# Sport_Analyzer_Chronojump.net
KiCad netlist of a schematic drawn in EAGLE
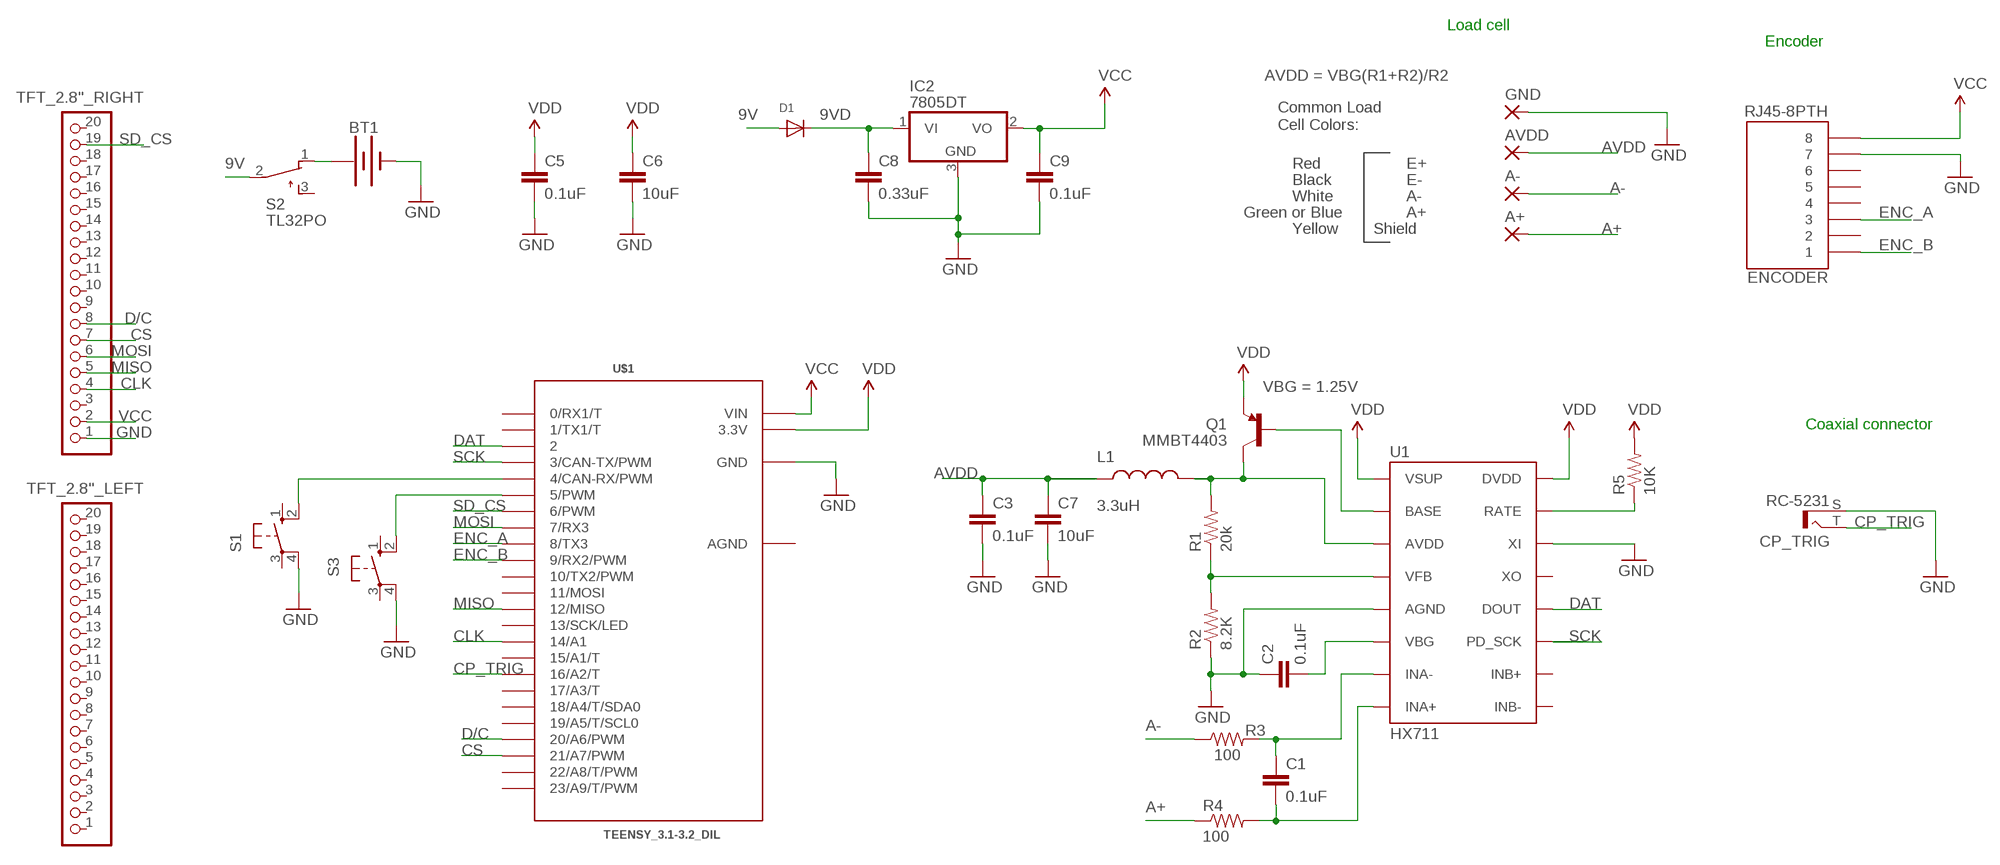
[diagram p0: schematic, sheet 1]

(export (version "E")
  (design (tool "Eeschema 10.0.6"))
  (components
    (comp (ref "A+")
      (value "3,81/1,4")
      (footprint "eagle-import:3,81_1,4")
      (libsource (lib "eagle-import") (part "3,81/1,4"))
    )
    (comp (ref "A-")
      (value "3,81/1,4")
      (footprint "eagle-import:3,81_1,4")
      (libsource (lib "eagle-import") (part "3,81/1,4"))
    )
    (comp (ref "AVDD")
      (value "3,81/1,4")
      (footprint "eagle-import:3,81_1,4")
      (libsource (lib "eagle-import") (part "3,81/1,4"))
    )
    (comp (ref "BT1")
      (value "BATTERY-9V")
      (footprint "eagle-import:BATTCON_9V")
      (libsource (lib "eagle-import") (part "BATTERY-9V"))
    )
    (comp (ref "C1")
      (value "0.1uF")
      (footprint "eagle-import:0603-CAP")
      (libsource (lib "eagle-import") (part "0.1UF-25V-5%(0603)"))
    )
    (comp (ref "C2")
      (value "0.1uF")
      (footprint "eagle-import:0603-CAP")
      (libsource (lib "eagle-import") (part "0.1UF-25V-5%(0603)"))
    )
    (comp (ref "C3")
      (value "0.1uF")
      (footprint "eagle-import:0603-CAP")
      (libsource (lib "eagle-import") (part "0.1UF-25V-5%(0603)"))
    )
    (comp (ref "C5")
      (value "0.1uF")
      (footprint "eagle-import:0603-CAP")
      (libsource (lib "eagle-import") (part "0.1UF-25V-5%(0603)"))
    )
    (comp (ref "C6")
      (value "10uF")
      (footprint "eagle-import:1210")
      (libsource (lib "eagle-import") (part "10UF50V20%(1210)"))
    )
    (comp (ref "C7")
      (value "10uF")
      (footprint "eagle-import:1210")
      (libsource (lib "eagle-import") (part "10UF50V20%(1210)"))
    )
    (comp (ref "C8")
      (value "0.33uF")
      (footprint "eagle-import:0603-CAP")
      (libsource (lib "eagle-import") (part "0.1UF-25V-5%(0603)"))
    )
    (comp (ref "C9")
      (value "0.1uF")
      (footprint "eagle-import:0603-CAP")
      (libsource (lib "eagle-import") (part "0.1UF-25V-5%(0603)"))
    )
    (comp (ref "CP_TRIG")
      (value "RC-5231")
      (footprint "eagle-import:RC-5231")
      (libsource (lib "eagle-import") (part "RC-5231"))
    )
    (comp (ref "D1")
      (value "DIODESOD-123")
      (footprint "eagle-import:SOD-123")
      (libsource (lib "eagle-import") (part "DIODESOD-123"))
    )
    (comp (ref "ENCODER")
      (value "RJ45-8PTH")
      (footprint "eagle-import:RJ45-8")
      (libsource (lib "eagle-import") (part "RJ45-8PTH"))
    )
    (comp (ref "GND")
      (value "3,81/1,4")
      (footprint "eagle-import:3,81_1,4")
      (libsource (lib "eagle-import") (part "3,81/1,4"))
    )
    (comp (ref "IC2")
      (value "7805DT")
      (footprint "eagle-import:TO252")
      (libsource (lib "eagle-import") (part "78DT05"))
    )
    (comp (ref "L1")
      (value "3.3uH")
      (footprint "eagle-import:0805")
      (libsource (lib "eagle-import") (part "INDUCTOR0805-IND"))
    )
    (comp (ref "Q1")
      (value "MMBT4403")
      (footprint "eagle-import:SOT23-3")
      (libsource (lib "eagle-import") (part "TRANSISTOR_PNPMMBT4403"))
    )
    (comp (ref "R1")
      (value "20k")
      (footprint "eagle-import:0603-RES")
      (libsource (lib "eagle-import") (part "20KOHM1/10W1%(0603)"))
    )
    (comp (ref "R2")
      (value "8.2K")
      (footprint "eagle-import:0603-RES")
      (libsource (lib "eagle-import") (part "8.2KOHM-1/10W-5%(0603)"))
    )
    (comp (ref "R3")
      (value "100")
      (footprint "eagle-import:0603-RES")
      (libsource (lib "eagle-import") (part "100OHM-1/10W-1%(0603)"))
    )
    (comp (ref "R4")
      (value "100")
      (footprint "eagle-import:0603-RES")
      (libsource (lib "eagle-import") (part "100OHM-1/10W-1%(0603)"))
    )
    (comp (ref "R5")
      (value "10K")
      (footprint "eagle-import:0603-RES")
      (libsource (lib "eagle-import") (part "10KOHM-1/10W-1%(0603)0603"))
    )
    (comp (ref "S1")
      (value "10-XX")
      (footprint "eagle-import:B3F-10XX")
      (fields (field (name "MPN") "B3F-1000"))
      (libsource (lib "eagle-import") (part "10-XX"))
    )
    (comp (ref "S2")
      (value "TL32PO")
      (footprint "eagle-import:TL3XPO")
      (libsource (lib "eagle-import") (part "TL32PO"))
    )
    (comp (ref "S3")
      (value "10-XX")
      (footprint "eagle-import:B3F-10XX")
      (fields (field (name "MPN") "B3F-1000"))
      (libsource (lib "eagle-import") (part "10-XX"))
    )
    (comp (ref "TFT_2.8\"_LEFT")
      (value "PINHD-1X20")
      (footprint "eagle-import:1X20")
      (libsource (lib "eagle-import") (part "PINHD-1X20"))
    )
    (comp (ref "TFT_2.8\"_RIGHT")
      (value "PINHD-1X20")
      (footprint "eagle-import:1X20")
      (libsource (lib "eagle-import") (part "PINHD-1X20"))
    )
    (comp (ref "U$1")
      (value "TEENSY_3.1-3.2_DIL")
      (footprint "eagle-import:TEENSY_3.0-3.2&LC_DIL")
      (libsource (lib "eagle-import") (part "TEENSY_3.1-3.2_DIL"))
    )
    (comp (ref "U1")
      (value "HX711")
      (footprint "eagle-import:SO16")
      (libsource (lib "eagle-import") (part "HX711HX711"))
    )
  )
  (nets
    (net (code "1") (name "/9V") (class "Default")
      (node (ref "D1") (pin "A") (pinfunction "A_A") (pintype "passive"))
      (node (ref "S2") (pin "2") (pinfunction "P_2") (pintype "passive"))
    )
    (net (code "2") (name "/9VD") (class "Default")
      (node (ref "C8") (pin "1") (pinfunction "1_1") (pintype "passive"))
      (node (ref "D1") (pin "C") (pinfunction "C_C") (pintype "passive"))
      (node (ref "IC2") (pin "1") (pinfunction "VI_1") (pintype "input"))
    )
    (net (code "3") (name "/A+") (class "Default")
      (node (ref "A+") (pin "1") (pinfunction "P_1") (pintype "passive"))
      (node (ref "R4") (pin "1") (pinfunction "1_1") (pintype "passive"))
    )
    (net (code "4") (name "/A-") (class "Default")
      (node (ref "A-") (pin "1") (pinfunction "P_1") (pintype "passive"))
      (node (ref "R3") (pin "1") (pinfunction "1_1") (pintype "passive"))
    )
    (net (code "5") (name "/AGND") (class "Default")
      (node (ref "U$1") (pin "AGND") (pinfunction "AGND_AGND") (pintype "power_in"))
    )
    (net (code "6") (name "/AVDD") (class "Default")
      (node (ref "AVDD") (pin "1") (pinfunction "P_1") (pintype "passive"))
      (node (ref "C3") (pin "1") (pinfunction "1_1") (pintype "passive"))
      (node (ref "C7") (pin "1") (pinfunction "1_1") (pintype "passive"))
      (node (ref "L1") (pin "1") (pinfunction "1_1") (pintype "passive"))
    )
    (net (code "7") (name "/CLK") (class "Default")
      (node (ref "TFT_2.8\"_RIGHT") (pin "4") (pinfunction "4_4") (pintype "passive"))
      (node (ref "U$1") (pin "14/A0") (pinfunction "14/A1_14/A0") (pintype "bidirectional"))
    )
    (net (code "8") (name "/CP_TRIG") (class "Default")
      (node (ref "CP_TRIG") (pin "T") (pinfunction "T_T") (pintype "passive"))
      (node (ref "U$1") (pin "16/A2") (pinfunction "16/A2/T_16/A2") (pintype "bidirectional"))
    )
    (net (code "9") (name "/CS") (class "Default")
      (node (ref "TFT_2.8\"_RIGHT") (pin "7") (pinfunction "7_7") (pintype "passive"))
      (node (ref "U$1") (pin "21/A7") (pinfunction "21/A7/PWM_21/A7") (pintype "bidirectional"))
    )
    (net (code "10") (name "/DAT") (class "Default")
      (node (ref "U$1") (pin "2") (pinfunction "2_2") (pintype "bidirectional"))
      (node (ref "U1") (pin "12") (pinfunction "DOUT_12") (pintype "bidirectional"))
    )
    (net (code "11") (name "/D{slash}C") (class "Default")
      (node (ref "TFT_2.8\"_RIGHT") (pin "8") (pinfunction "8_8") (pintype "passive"))
      (node (ref "U$1") (pin "20/A6") (pinfunction "20/A6/PWM_20/A6") (pintype "bidirectional"))
    )
    (net (code "12") (name "/ENC_A") (class "Default")
      (node (ref "ENCODER") (pin "3") (pinfunction "3_3") (pintype "bidirectional"))
      (node (ref "U$1") (pin "8") (pinfunction "8/TX3_8") (pintype "bidirectional"))
    )
    (net (code "13") (name "/ENC_B") (class "Default")
      (node (ref "ENCODER") (pin "1") (pinfunction "1_1") (pintype "bidirectional"))
      (node (ref "U$1") (pin "9") (pinfunction "9/RX2/PWM_9") (pintype "bidirectional"))
    )
    (net (code "14") (name "/MISO") (class "Default")
      (node (ref "TFT_2.8\"_RIGHT") (pin "5") (pinfunction "5_5") (pintype "passive"))
      (node (ref "U$1") (pin "12") (pinfunction "12/MISO_12") (pintype "bidirectional"))
    )
    (net (code "15") (name "/MOSI") (class "Default")
      (node (ref "TFT_2.8\"_RIGHT") (pin "6") (pinfunction "6_6") (pintype "passive"))
      (node (ref "U$1") (pin "7") (pinfunction "7/RX3_7") (pintype "bidirectional"))
    )
    (net (code "16") (name "/SCK") (class "Default")
      (node (ref "U$1") (pin "3") (pinfunction "3/CAN-TX/PWM_3") (pintype "bidirectional"))
      (node (ref "U1") (pin "11") (pinfunction "PD_SCK_11") (pintype "bidirectional"))
    )
    (net (code "17") (name "/SD_CS") (class "Default")
      (node (ref "TFT_2.8\"_RIGHT") (pin "19") (pinfunction "19_19") (pintype "passive"))
      (node (ref "U$1") (pin "6") (pinfunction "6/PWM_6") (pintype "bidirectional"))
    )
    (net (code "18") (name "GND") (class "Default")
      (node (ref "BT1") (pin "-") (pinfunction "-_-") (pintype "power_in"))
      (node (ref "C2") (pin "1") (pinfunction "1_1") (pintype "passive"))
      (node (ref "C3") (pin "2") (pinfunction "2_2") (pintype "passive"))
      (node (ref "C5") (pin "2") (pinfunction "2_2") (pintype "passive"))
      (node (ref "C6") (pin "2") (pinfunction "2_2") (pintype "passive"))
      (node (ref "C7") (pin "2") (pinfunction "2_2") (pintype "passive"))
      (node (ref "C8") (pin "2") (pinfunction "2_2") (pintype "passive"))
      (node (ref "C9") (pin "2") (pinfunction "2_2") (pintype "passive"))
      (node (ref "CP_TRIG") (pin "S") (pinfunction "S_S") (pintype "passive"))
      (node (ref "ENCODER") (pin "7") (pinfunction "7_7") (pintype "bidirectional"))
      (node (ref "GND") (pin "1") (pinfunction "P_1") (pintype "passive"))
      (node (ref "IC2") (pin "3") (pinfunction "GND_3") (pintype "passive"))
      (node (ref "R2") (pin "1") (pinfunction "1_1") (pintype "passive"))
      (node (ref "S1") (pin "4") (pinfunction "P1_4") (pintype "passive"))
      (node (ref "S3") (pin "4") (pinfunction "P1_4") (pintype "passive"))
      (node (ref "TFT_2.8\"_RIGHT") (pin "1") (pinfunction "1_1") (pintype "passive"))
      (node (ref "U$1") (pin "GND") (pinfunction "GND_GND") (pintype "power_in"))
      (node (ref "U1") (pin "14") (pinfunction "XI_14") (pintype "bidirectional"))
      (node (ref "U1") (pin "5") (pinfunction "AGND_5") (pintype "bidirectional"))
    )
    (net (code "19") (name "Net-(Q1-B)") (class "Default")
      (node (ref "Q1") (pin "1") (pinfunction "B_1") (pintype "passive"))
      (node (ref "U1") (pin "2") (pinfunction "BASE_2") (pintype "bidirectional"))
    )
    (net (code "20") (name "Net-(Q1-C)") (class "Default")
      (node (ref "L1") (pin "2") (pinfunction "2_2") (pintype "passive"))
      (node (ref "Q1") (pin "3") (pinfunction "C_3") (pintype "passive"))
      (node (ref "R1") (pin "2") (pinfunction "2_2") (pintype "passive"))
      (node (ref "U1") (pin "3") (pinfunction "AVDD_3") (pintype "bidirectional"))
    )
    (net (code "21") (name "Net-(S1-S1)") (class "Default")
      (node (ref "S1") (pin "2") (pinfunction "S1_2") (pintype "passive"))
      (node (ref "U$1") (pin "4") (pinfunction "4/CAN-RX/PWM_4") (pintype "bidirectional"))
    )
    (net (code "22") (name "Net-(S2-O)") (class "Default")
      (node (ref "BT1") (pin "+") (pinfunction "+_+") (pintype "power_in"))
      (node (ref "S2") (pin "1") (pinfunction "O_1") (pintype "passive"))
    )
    (net (code "23") (name "Net-(S3-S1)") (class "Default")
      (node (ref "S3") (pin "2") (pinfunction "S1_2") (pintype "passive"))
      (node (ref "U$1") (pin "5") (pinfunction "5/PWM_5") (pintype "bidirectional"))
    )
    (net (code "24") (name "Net-(U1-INA+)") (class "Default")
      (node (ref "C1") (pin "2") (pinfunction "2_2") (pintype "passive"))
      (node (ref "R4") (pin "2") (pinfunction "2_2") (pintype "passive"))
      (node (ref "U1") (pin "8") (pinfunction "INA+_8") (pintype "bidirectional"))
    )
    (net (code "25") (name "Net-(U1-INA-)") (class "Default")
      (node (ref "C1") (pin "1") (pinfunction "1_1") (pintype "passive"))
      (node (ref "R3") (pin "2") (pinfunction "2_2") (pintype "passive"))
      (node (ref "U1") (pin "7") (pinfunction "INA-_7") (pintype "bidirectional"))
    )
    (net (code "26") (name "Net-(U1-RATE)") (class "Default")
      (node (ref "R5") (pin "1") (pinfunction "1_1") (pintype "passive"))
      (node (ref "U1") (pin "15") (pinfunction "RATE_15") (pintype "bidirectional"))
    )
    (net (code "27") (name "Net-(U1-VBG)") (class "Default")
      (node (ref "C2") (pin "2") (pinfunction "2_2") (pintype "passive"))
      (node (ref "U1") (pin "6") (pinfunction "VBG_6") (pintype "bidirectional"))
    )
    (net (code "28") (name "Net-(U1-VFB)") (class "Default")
      (node (ref "R1") (pin "1") (pinfunction "1_1") (pintype "passive"))
      (node (ref "R2") (pin "2") (pinfunction "2_2") (pintype "passive"))
      (node (ref "U1") (pin "4") (pinfunction "VFB_4") (pintype "bidirectional"))
    )
    (net (code "29") (name "VCC") (class "Default")
      (node (ref "C9") (pin "1") (pinfunction "1_1") (pintype "passive"))
      (node (ref "ENCODER") (pin "8") (pinfunction "8_8") (pintype "bidirectional"))
      (node (ref "IC2") (pin "2") (pinfunction "VO_2") (pintype "passive"))
      (node (ref "TFT_2.8\"_RIGHT") (pin "2") (pinfunction "2_2") (pintype "passive"))
      (node (ref "U$1") (pin "VIN") (pinfunction "VIN_VIN") (pintype "power_in"))
    )
    (net (code "30") (name "VDD") (class "Default")
      (node (ref "C5") (pin "1") (pinfunction "1_1") (pintype "passive"))
      (node (ref "C6") (pin "1") (pinfunction "1_1") (pintype "passive"))
      (node (ref "Q1") (pin "2") (pinfunction "E_2") (pintype "passive"))
      (node (ref "R5") (pin "2") (pinfunction "2_2") (pintype "passive"))
      (node (ref "U$1") (pin "3.3V") (pinfunction "3.3V_3.3V") (pintype "power_in"))
      (node (ref "U1") (pin "1") (pinfunction "VSUP_1") (pintype "bidirectional"))
      (node (ref "U1") (pin "16") (pinfunction "DVDD_16") (pintype "bidirectional"))
    )
    (net (code "31") (name "unconnected-(ENCODER-Pad2)") (class "Default")
      (node (ref "ENCODER") (pin "2") (pinfunction "2_2") (pintype "bidirectional"))
    )
    (net (code "32") (name "unconnected-(ENCODER-Pad4)") (class "Default")
      (node (ref "ENCODER") (pin "4") (pinfunction "4_4") (pintype "bidirectional"))
    )
    (net (code "33") (name "unconnected-(ENCODER-Pad5)") (class "Default")
      (node (ref "ENCODER") (pin "5") (pinfunction "5_5") (pintype "bidirectional"))
    )
    (net (code "34") (name "unconnected-(ENCODER-Pad6)") (class "Default")
      (node (ref "ENCODER") (pin "6") (pinfunction "6_6") (pintype "bidirectional"))
    )
    (net (code "35") (name "unconnected-(S1-P-Pad3)") (class "Default")
      (node (ref "S1") (pin "3") (pinfunction "P_3") (pintype "passive"))
    )
    (net (code "36") (name "unconnected-(S1-S-Pad1)") (class "Default")
      (node (ref "S1") (pin "1") (pinfunction "S_1") (pintype "passive"))
    )
    (net (code "37") (name "unconnected-(S2-S-Pad3)") (class "Default")
      (node (ref "S2") (pin "3") (pinfunction "S_3") (pintype "passive"))
    )
    (net (code "38") (name "unconnected-(S3-P-Pad3)") (class "Default")
      (node (ref "S3") (pin "3") (pinfunction "P_3") (pintype "passive"))
    )
    (net (code "39") (name "unconnected-(S3-S-Pad1)") (class "Default")
      (node (ref "S3") (pin "1") (pinfunction "S_1") (pintype "passive"))
    )
    (net (code "40") (name "unconnected-(TFT_2.8\"_LEFT-Pad1)") (class "Default")
      (node (ref "TFT_2.8\"_LEFT") (pin "1") (pinfunction "1_1") (pintype "passive"))
    )
    (net (code "41") (name "unconnected-(TFT_2.8\"_LEFT-Pad2)") (class "Default")
      (node (ref "TFT_2.8\"_LEFT") (pin "2") (pinfunction "2_2") (pintype "passive"))
    )
    (net (code "42") (name "unconnected-(TFT_2.8\"_LEFT-Pad3)") (class "Default")
      (node (ref "TFT_2.8\"_LEFT") (pin "3") (pinfunction "3_3") (pintype "passive"))
    )
    (net (code "43") (name "unconnected-(TFT_2.8\"_LEFT-Pad4)") (class "Default")
      (node (ref "TFT_2.8\"_LEFT") (pin "4") (pinfunction "4_4") (pintype "passive"))
    )
    (net (code "44") (name "unconnected-(TFT_2.8\"_LEFT-Pad5)") (class "Default")
      (node (ref "TFT_2.8\"_LEFT") (pin "5") (pinfunction "5_5") (pintype "passive"))
    )
    (net (code "45") (name "unconnected-(TFT_2.8\"_LEFT-Pad6)") (class "Default")
      (node (ref "TFT_2.8\"_LEFT") (pin "6") (pinfunction "6_6") (pintype "passive"))
    )
    (net (code "46") (name "unconnected-(TFT_2.8\"_LEFT-Pad7)") (class "Default")
      (node (ref "TFT_2.8\"_LEFT") (pin "7") (pinfunction "7_7") (pintype "passive"))
    )
    (net (code "47") (name "unconnected-(TFT_2.8\"_LEFT-Pad8)") (class "Default")
      (node (ref "TFT_2.8\"_LEFT") (pin "8") (pinfunction "8_8") (pintype "passive"))
    )
    (net (code "48") (name "unconnected-(TFT_2.8\"_LEFT-Pad9)") (class "Default")
      (node (ref "TFT_2.8\"_LEFT") (pin "9") (pinfunction "9_9") (pintype "passive"))
    )
    (net (code "49") (name "unconnected-(TFT_2.8\"_LEFT-Pad10)") (class "Default")
      (node (ref "TFT_2.8\"_LEFT") (pin "10") (pinfunction "10_10") (pintype "passive"))
    )
    (net (code "50") (name "unconnected-(TFT_2.8\"_LEFT-Pad11)") (class "Default")
      (node (ref "TFT_2.8\"_LEFT") (pin "11") (pinfunction "11_11") (pintype "passive"))
    )
    (net (code "51") (name "unconnected-(TFT_2.8\"_LEFT-Pad12)") (class "Default")
      (node (ref "TFT_2.8\"_LEFT") (pin "12") (pinfunction "12_12") (pintype "passive"))
    )
    (net (code "52") (name "unconnected-(TFT_2.8\"_LEFT-Pad13)") (class "Default")
      (node (ref "TFT_2.8\"_LEFT") (pin "13") (pinfunction "13_13") (pintype "passive"))
    )
    (net (code "53") (name "unconnected-(TFT_2.8\"_LEFT-Pad14)") (class "Default")
      (node (ref "TFT_2.8\"_LEFT") (pin "14") (pinfunction "14_14") (pintype "passive"))
    )
    (net (code "54") (name "unconnected-(TFT_2.8\"_LEFT-Pad15)") (class "Default")
      (node (ref "TFT_2.8\"_LEFT") (pin "15") (pinfunction "15_15") (pintype "passive"))
    )
    (net (code "55") (name "unconnected-(TFT_2.8\"_LEFT-Pad16)") (class "Default")
      (node (ref "TFT_2.8\"_LEFT") (pin "16") (pinfunction "16_16") (pintype "passive"))
    )
    (net (code "56") (name "unconnected-(TFT_2.8\"_LEFT-Pad17)") (class "Default")
      (node (ref "TFT_2.8\"_LEFT") (pin "17") (pinfunction "17_17") (pintype "passive"))
    )
    (net (code "57") (name "unconnected-(TFT_2.8\"_LEFT-Pad18)") (class "Default")
      (node (ref "TFT_2.8\"_LEFT") (pin "18") (pinfunction "18_18") (pintype "passive"))
    )
    (net (code "58") (name "unconnected-(TFT_2.8\"_LEFT-Pad19)") (class "Default")
      (node (ref "TFT_2.8\"_LEFT") (pin "19") (pinfunction "19_19") (pintype "passive"))
    )
    (net (code "59") (name "unconnected-(TFT_2.8\"_LEFT-Pad20)") (class "Default")
      (node (ref "TFT_2.8\"_LEFT") (pin "20") (pinfunction "20_20") (pintype "passive"))
    )
    (net (code "60") (name "unconnected-(TFT_2.8\"_RIGHT-Pad3)") (class "Default")
      (node (ref "TFT_2.8\"_RIGHT") (pin "3") (pinfunction "3_3") (pintype "passive"))
    )
    (net (code "61") (name "unconnected-(TFT_2.8\"_RIGHT-Pad9)") (class "Default")
      (node (ref "TFT_2.8\"_RIGHT") (pin "9") (pinfunction "9_9") (pintype "passive"))
    )
    (net (code "62") (name "unconnected-(TFT_2.8\"_RIGHT-Pad10)") (class "Default")
      (node (ref "TFT_2.8\"_RIGHT") (pin "10") (pinfunction "10_10") (pintype "passive"))
    )
    (net (code "63") (name "unconnected-(TFT_2.8\"_RIGHT-Pad11)") (class "Default")
      (node (ref "TFT_2.8\"_RIGHT") (pin "11") (pinfunction "11_11") (pintype "passive"))
    )
    (net (code "64") (name "unconnected-(TFT_2.8\"_RIGHT-Pad12)") (class "Default")
      (node (ref "TFT_2.8\"_RIGHT") (pin "12") (pinfunction "12_12") (pintype "passive"))
    )
    (net (code "65") (name "unconnected-(TFT_2.8\"_RIGHT-Pad13)") (class "Default")
      (node (ref "TFT_2.8\"_RIGHT") (pin "13") (pinfunction "13_13") (pintype "passive"))
    )
    (net (code "66") (name "unconnected-(TFT_2.8\"_RIGHT-Pad14)") (class "Default")
      (node (ref "TFT_2.8\"_RIGHT") (pin "14") (pinfunction "14_14") (pintype "passive"))
    )
    (net (code "67") (name "unconnected-(TFT_2.8\"_RIGHT-Pad15)") (class "Default")
      (node (ref "TFT_2.8\"_RIGHT") (pin "15") (pinfunction "15_15") (pintype "passive"))
    )
    (net (code "68") (name "unconnected-(TFT_2.8\"_RIGHT-Pad16)") (class "Default")
      (node (ref "TFT_2.8\"_RIGHT") (pin "16") (pinfunction "16_16") (pintype "passive"))
    )
    (net (code "69") (name "unconnected-(TFT_2.8\"_RIGHT-Pad17)") (class "Default")
      (node (ref "TFT_2.8\"_RIGHT") (pin "17") (pinfunction "17_17") (pintype "passive"))
    )
    (net (code "70") (name "unconnected-(TFT_2.8\"_RIGHT-Pad18)") (class "Default")
      (node (ref "TFT_2.8\"_RIGHT") (pin "18") (pinfunction "18_18") (pintype "passive"))
    )
    (net (code "71") (name "unconnected-(TFT_2.8\"_RIGHT-Pad20)") (class "Default")
      (node (ref "TFT_2.8\"_RIGHT") (pin "20") (pinfunction "20_20") (pintype "passive"))
    )
    (net (code "72") (name "unconnected-(U$1-0{slash}RX1{slash}T-Pad0)") (class "Default")
      (node (ref "U$1") (pin "0") (pinfunction "0/RX1/T_0") (pintype "bidirectional"))
    )
    (net (code "73") (name "unconnected-(U$1-1{slash}TX1{slash}T-Pad1)") (class "Default")
      (node (ref "U$1") (pin "1") (pinfunction "1/TX1/T_1") (pintype "bidirectional"))
    )
    (net (code "74") (name "unconnected-(U$1-10{slash}TX2{slash}PWM-Pad10)") (class "Default")
      (node (ref "U$1") (pin "10") (pinfunction "10/TX2/PWM_10") (pintype "bidirectional"))
    )
    (net (code "75") (name "unconnected-(U$1-11{slash}MOSI-Pad11)") (class "Default")
      (node (ref "U$1") (pin "11") (pinfunction "11/MOSI_11") (pintype "bidirectional"))
    )
    (net (code "76") (name "unconnected-(U$1-13{slash}SCK{slash}LED-Pad13)") (class "Default")
      (node (ref "U$1") (pin "13") (pinfunction "13/SCK/LED_13") (pintype "bidirectional"))
    )
    (net (code "77") (name "unconnected-(U$1-15{slash}A1{slash}T-Pad15{slash}A1)") (class "Default")
      (node (ref "U$1") (pin "15/A1") (pinfunction "15/A1/T_15/A1") (pintype "bidirectional"))
    )
    (net (code "78") (name "unconnected-(U$1-17{slash}A3{slash}T-Pad17{slash}A3)") (class "Default")
      (node (ref "U$1") (pin "17/A3") (pinfunction "17/A3/T_17/A3") (pintype "bidirectional"))
    )
    (net (code "79") (name "unconnected-(U$1-18{slash}A4{slash}T{slash}SDA0-Pad18{slash}A4)") (class "Default")
      (node (ref "U$1") (pin "18/A4") (pinfunction "18/A4/T/SDA0_18/A4") (pintype "bidirectional"))
    )
    (net (code "80") (name "unconnected-(U$1-19{slash}A5{slash}T{slash}SCL0-Pad19{slash}A5)") (class "Default")
      (node (ref "U$1") (pin "19/A5") (pinfunction "19/A5/T/SCL0_19/A5") (pintype "bidirectional"))
    )
    (net (code "81") (name "unconnected-(U$1-22{slash}A8{slash}T{slash}PWM-Pad22{slash}A8)") (class "Default")
      (node (ref "U$1") (pin "22/A8") (pinfunction "22/A8/T/PWM_22/A8") (pintype "bidirectional"))
    )
    (net (code "82") (name "unconnected-(U$1-23{slash}A9{slash}T{slash}PWM-Pad23{slash}A9)") (class "Default")
      (node (ref "U$1") (pin "23/A9") (pinfunction "23/A9/T/PWM_23/A9") (pintype "bidirectional"))
    )
    (net (code "83") (name "unconnected-(U1-INB+-Pad10)") (class "Default")
      (node (ref "U1") (pin "10") (pinfunction "INB+_10") (pintype "bidirectional"))
    )
    (net (code "84") (name "unconnected-(U1-INB--Pad9)") (class "Default")
      (node (ref "U1") (pin "9") (pinfunction "INB-_9") (pintype "bidirectional"))
    )
    (net (code "85") (name "unconnected-(U1-XO-Pad13)") (class "Default")
      (node (ref "U1") (pin "13") (pinfunction "XO_13") (pintype "bidirectional"))
    )
  )
)
